# CH32F_V208G-R0.net
KiCad netlist of a schematic drawn in Altium Designer
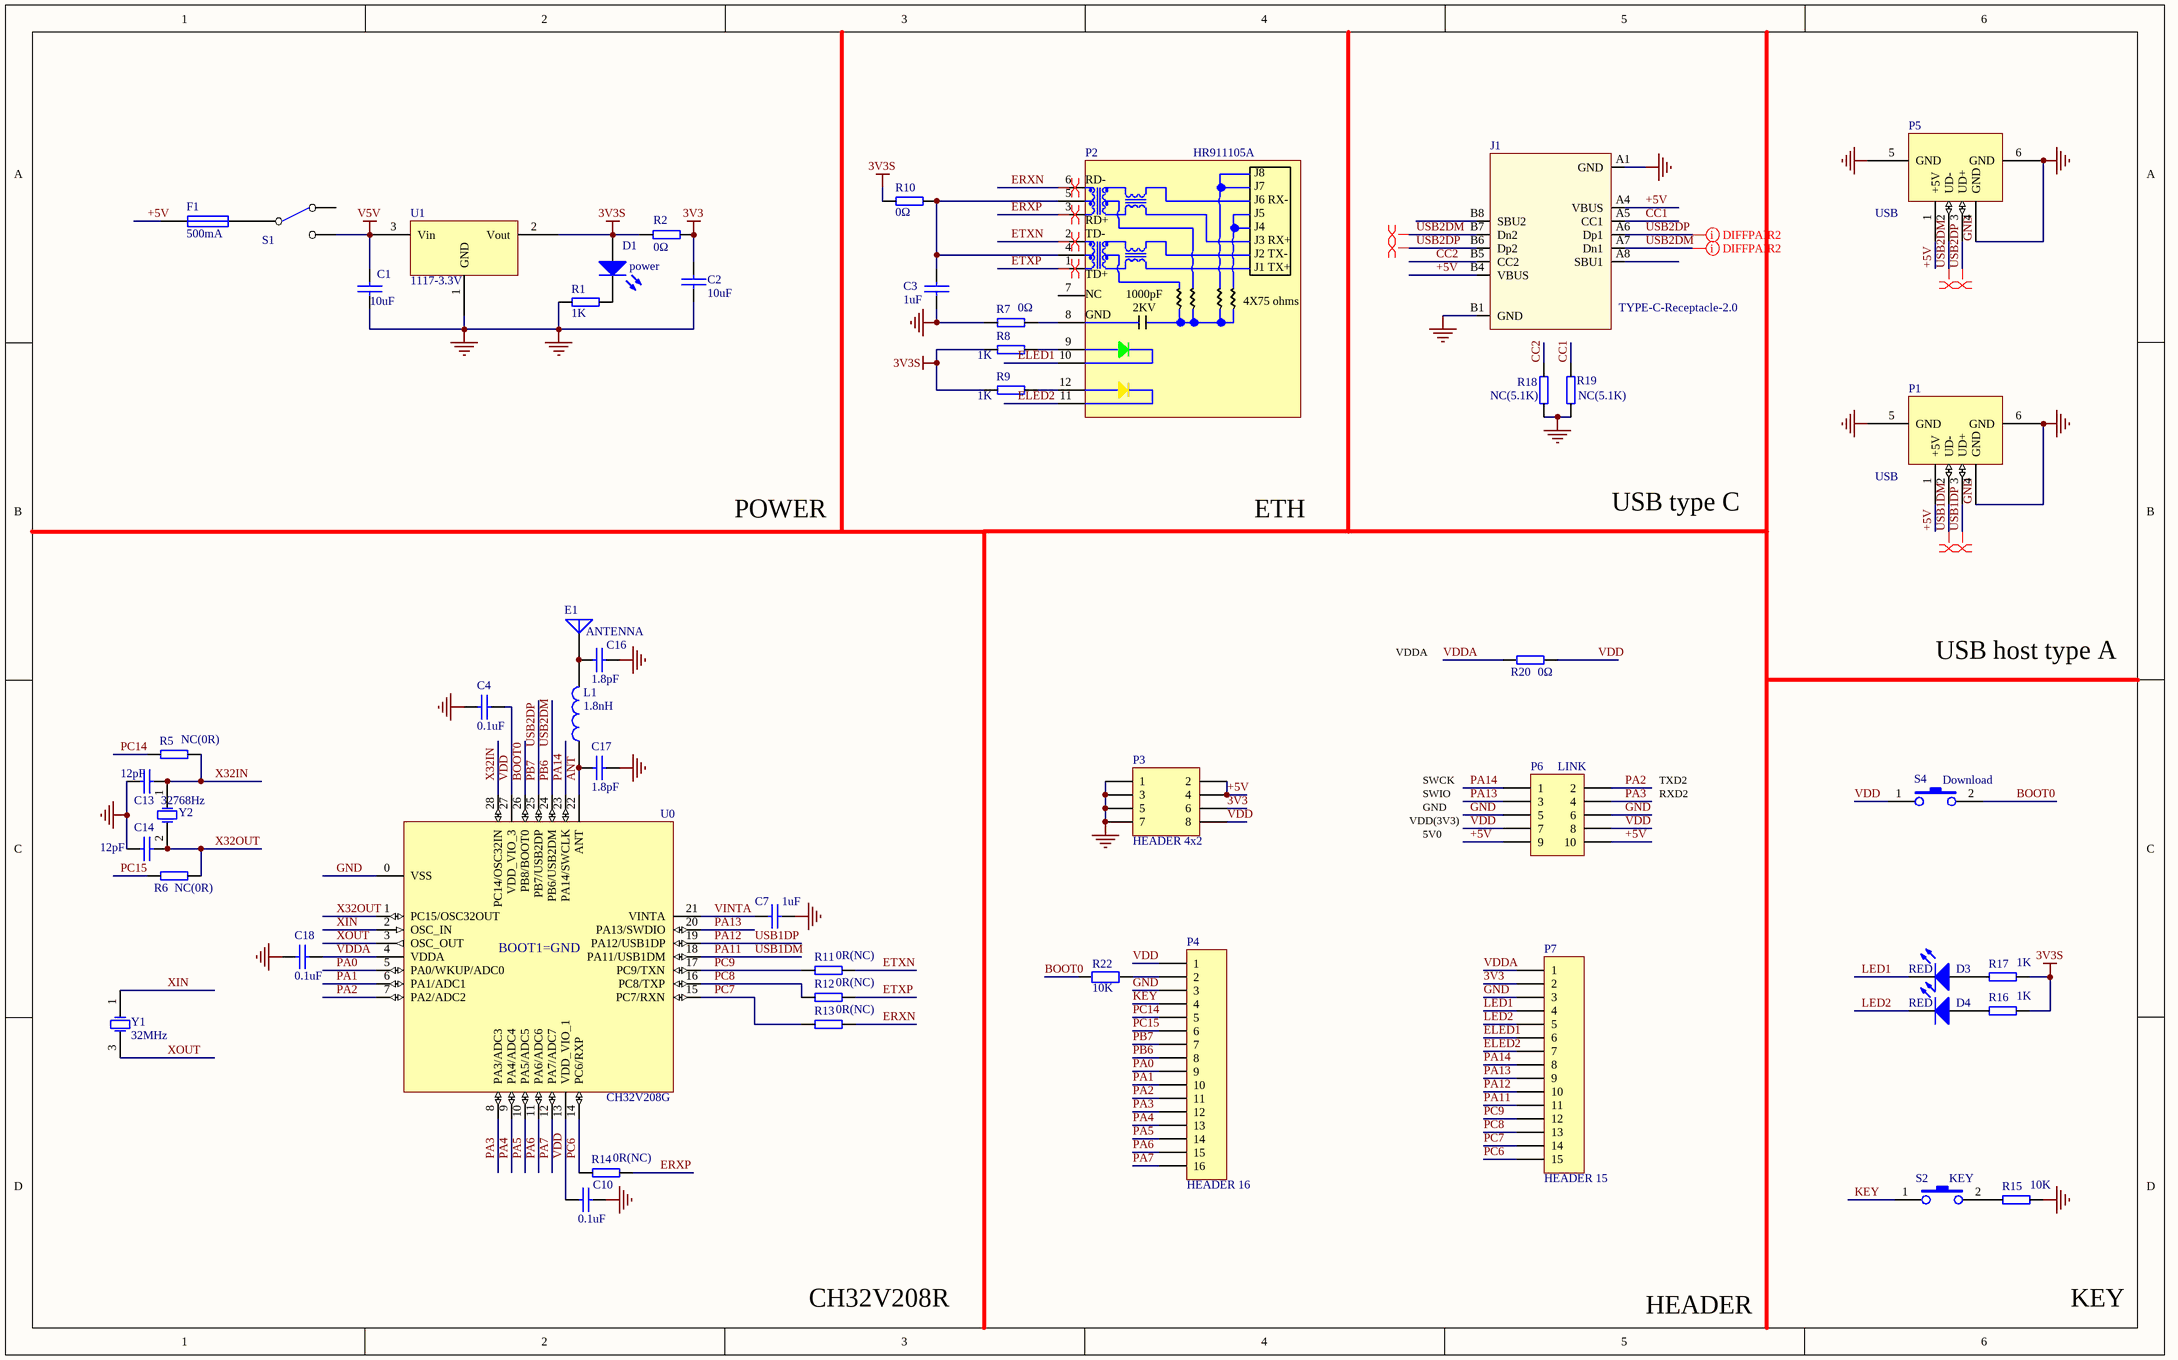
[diagram p0: CH32F&V208G-R0.SchDoc]

(export (version "E")
  (design (tool "Eeschema 10.0.6"))
  (components
    (comp (ref "C1")
      (value "10uF")
      (footprint "3216_C")
      (description "Capacitor")
      (libsource (lib "") (part "CAP_1"))
    )
    (comp (ref "C2")
      (value "10uF")
      (footprint "0603_C")
      (description "Capacitor")
      (libsource (lib "") (part "CAP_1"))
    )
    (comp (ref "C3")
      (value "1uF")
      (footprint "0603_C")
      (description "Capacitor")
      (libsource (lib "") (part "CAP_1"))
    )
    (comp (ref "C4")
      (value "0.1uF")
      (footprint "0603_C")
      (description "Capacitor")
      (libsource (lib "*") (part "CAP"))
    )
    (comp (ref "C7")
      (value "1uF")
      (footprint "0603_C")
      (description "Capacitor")
      (libsource (lib "*") (part "CAP"))
    )
    (comp (ref "C10")
      (value "0.1uF")
      (footprint "0603_C")
      (description "Capacitor")
      (libsource (lib "*") (part "CAP"))
    )
    (comp (ref "C13")
      (value "12pF")
      (footprint "0603_C")
      (description "Capacitor")
      (libsource (lib "") (part "CAP_1"))
    )
    (comp (ref "C14")
      (value "12pF")
      (footprint "0603_C")
      (description "Capacitor")
      (libsource (lib "") (part "CAP_1"))
    )
    (comp (ref "C16")
      (value "1.8pF")
      (footprint "0603_C")
      (description "Capacitor")
      (libsource (lib "*") (part "CAP"))
    )
    (comp (ref "C17")
      (value "1.8pF")
      (footprint "0603_C")
      (description "Capacitor")
      (libsource (lib "*") (part "CAP"))
    )
    (comp (ref "C18")
      (value "0.1uF")
      (footprint "0603_C")
      (description "Capacitor")
      (libsource (lib "*") (part "CAP"))
    )
    (comp (ref "D1")
      (value "power")
      (footprint "0603+")
      (description "Typical INFRARED GaAs LED")
      (fields (field (name "PUBLISHER") "Altium Limited"))
      (libsource (lib "*") (part "LED0"))
    )
    (comp (ref "D3")
      (value "RED")
      (footprint "0603+")
      (description "Typical INFRARED GaAs LED")
      (fields (field (name "PUBLISHER") "Altium Limited"))
      (libsource (lib "*") (part "LED0"))
    )
    (comp (ref "D4")
      (value "RED")
      (footprint "0603+")
      (description "Typical INFRARED GaAs LED")
      (fields (field (name "PUBLISHER") "Altium Limited"))
      (libsource (lib "*") (part "LED0"))
    )
    (comp (ref "E1")
      (value "ANTENNA")
      (footprint "ANT-F-1-2.4G-1.6mmFR4")
      (description "Generic Antenna")
      (libsource (lib "*") (part "ANTENNA"))
    )
    (comp (ref "F1")
      (value "500mA")
      (footprint "0603")
      (description "Fuse")
      (libsource (lib "wch_sch_others") (part "FUSE1"))
    )
    (comp (ref "J1")
      (value "TYPE-C-Receptacle-2.0")
      (footprint "TYPE-C-Receptacle-2.0")
      (description "Type-C USB2.0 母座")
      (libsource (lib "Miscellaneous SCH Lib") (part "TYPE-C-Receptacle-2.0"))
    )
    (comp (ref "L1") (value "1.8nH") (footprint "0603") (libsource (lib "*") (part "INDUCTOR")))
    (comp (ref "P1")
      (value "USB")
      (footprint "USBAF")
      (description "USB Port")
      (libsource (lib "*") (part "USB"))
    )
    (comp (ref "P2") (value "HR911105A") (footprint "HR911105A") (libsource (lib "*") (part "HR911105A")))
    (comp (ref "P3")
      (value "HEADER 4x2")
      (footprint "MYPCB:IDC8-2.54mm")
      (description "Header, 4-Pin, Dual row")
      (libsource (lib "wch_sch_others") (part "HEADER 4x2"))
    )
    (comp (ref "P4")
      (value "HEADER 16")
      (footprint "SIP16-2.54mm")
      (description "Header, 16-Pin")
      (libsource (lib "wch_sch_others") (part "HEADER 16"))
    )
    (comp (ref "P5")
      (value "USB")
      (footprint "USBAF")
      (description "USB Port")
      (libsource (lib "*") (part "USB"))
    )
    (comp (ref "P6")
      (value "LINK")
      (footprint "IDC10-2.54mm")
      (description "Header, 5-Pin, Dual row, Right Angle")
      (fields (field (name "PUBLISHER") "Altium Limited"))
      (libsource (lib "Miscellaneous Connectors") (part "Header 5X2H"))
    )
    (comp (ref "P7")
      (value "HEADER 15")
      (footprint "SIP15-2.54mm")
      (description "Header, 15-Pin")
      (libsource (lib "wch_sch_others") (part "HEADER 15"))
    )
    (comp (ref "R1") (value "1K") (footprint "0603") (libsource (lib "wch_sch_others") (part "RES")))
    (comp (ref "R2") (value "0Ω") (footprint "0603") (libsource (lib "wch_sch_others") (part "RES")))
    (comp (ref "R5") (value "NC(0R)") (footprint "0603") (libsource (lib "wch_sch_others") (part "RES")))
    (comp (ref "R6") (value "NC(0R)") (footprint "0603") (libsource (lib "wch_sch_others") (part "RES")))
    (comp (ref "R7") (value "0Ω") (footprint "0603") (libsource (lib "wch_sch_others") (part "RES")))
    (comp (ref "R8") (value "1K") (footprint "0603") (libsource (lib "wch_sch_others") (part "RES")))
    (comp (ref "R9") (value "1K") (footprint "0603") (libsource (lib "wch_sch_others") (part "RES")))
    (comp (ref "R10") (value "0Ω") (footprint "0603") (libsource (lib "wch_sch_others") (part "RES")))
    (comp (ref "R11") (value "0R(NC)") (footprint "0603") (libsource (lib "wch_sch_others") (part "RES")))
    (comp (ref "R12") (value "0R(NC)") (footprint "0603") (libsource (lib "wch_sch_others") (part "RES")))
    (comp (ref "R13") (value "0R(NC)") (footprint "0603") (libsource (lib "wch_sch_others") (part "RES")))
    (comp (ref "R14") (value "0R(NC)") (footprint "0603") (libsource (lib "wch_sch_others") (part "RES")))
    (comp (ref "R15") (value "10K") (footprint "0603") (libsource (lib "wch_sch_others") (part "RES")))
    (comp (ref "R16") (value "1K") (footprint "0603") (libsource (lib "wch_sch_others") (part "RES")))
    (comp (ref "R17") (value "1K") (footprint "0603") (libsource (lib "wch_sch_others") (part "RES")))
    (comp (ref "R18") (value "NC(5.1K)") (footprint "0603") (libsource (lib "wch_sch_others") (part "RES")))
    (comp (ref "R19") (value "NC(5.1K)") (footprint "0603") (libsource (lib "wch_sch_others") (part "RES")))
    (comp (ref "R20") (value "0Ω") (footprint "0603") (libsource (lib "*") (part "R")))
    (comp (ref "R22")
      (value "10K")
      (footprint "0603")
      (description "Resistor")
      (libsource (lib "Miscellaneous Devices") (part "Res2"))
    )
    (comp (ref "S1") (value "SW SPDT") (footprint "SW1") (libsource (lib "*") (part "SW SPDT")))
    (comp (ref "S2")
      (value "KEY")
      (footprint "SMD_6.1x3.65x2.5mm-KEY")
      (libsource (lib "wch_sch_others") (part "KEY1"))
    )
    (comp (ref "S4")
      (value "Download")
      (footprint "SMD_6.1x3.65x2.5mm-KEY")
      (libsource (lib "wch_sch_others") (part "KEY1"))
    )
    (comp (ref "U0")
      (value "CH32V208G")
      (footprint "QFN28_4x4")
      (description "RISC-V BLE5.3 MCU, 10M Ethernet, 2*USB, CAN")
      (libsource (lib "CHXXX") (part "CH32V208G"))
    )
    (comp (ref "U1")
      (value "1117-3.3V")
      (footprint "SOT-223")
      (libsource (lib "wch_sch_others") (part "1117-3.3V"))
    )
    (comp (ref "Y1")
      (value "32MHz")
      (footprint "XT3225")
      (description "Crystal Oscillator")
      (fields (field (name "PUBLISHER") "Altium Limited"))
      (libsource (lib "") (part "XTAL_1"))
    )
    (comp (ref "Y2")
      (value "32768Hz")
      (footprint "FC-135")
      (description "Crystal Oscillator")
      (fields (field (name "PUBLISHER") "Altium Limited"))
      (libsource (lib "*") (part "XTAL"))
    )
  )
  (nets
    (net (code "1") (name "/+5V") (class "Default")
      (node (ref "F1") (pin "1") (pinfunction "1_1") (pintype "passive"))
      (node (ref "J1") (pin "A4") (pinfunction "VBUS_A4") (pintype "passive"))
      (node (ref "J1") (pin "B4") (pinfunction "VBUS_B4") (pintype "passive"))
      (node (ref "P1") (pin "1") (pinfunction "+5V_1") (pintype "power_in"))
      (node (ref "P3") (pin "2") (pinfunction "2_2") (pintype "passive"))
      (node (ref "P3") (pin "4") (pinfunction "4_4") (pintype "passive"))
      (node (ref "P5") (pin "1") (pinfunction "+5V_1") (pintype "power_in"))
      (node (ref "P6") (pin "10") (pinfunction "10_10") (pintype "passive"))
      (node (ref "P6") (pin "9") (pinfunction "9_9") (pintype "passive"))
    )
    (net (code "2") (name "/ANT") (class "Default")
      (node (ref "C17") (pin "2") (pinfunction "2_2") (pintype "passive"))
      (node (ref "L1") (pin "1") (pinfunction "1_1") (pintype "passive"))
      (node (ref "U0") (pin "22") (pinfunction "ANT_22") (pintype "power_in"))
    )
    (net (code "3") (name "/BOOT0") (class "Default")
      (node (ref "R22") (pin "1") (pinfunction "1_1") (pintype "passive"))
      (node (ref "S4") (pin "2") (pinfunction "2_2") (pintype "passive"))
      (node (ref "U0") (pin "26") (pinfunction "PB8/BOOT0_26") (pintype "bidirectional"))
    )
    (net (code "4") (name "/CC1") (class "Default")
      (node (ref "J1") (pin "A5") (pinfunction "CC1_A5") (pintype "passive"))
      (node (ref "R19") (pin "1") (pintype "passive"))
    )
    (net (code "5") (name "/CC2") (class "Default")
      (node (ref "J1") (pin "B5") (pinfunction "CC2_B5") (pintype "passive"))
      (node (ref "R18") (pin "1") (pintype "passive"))
    )
    (net (code "6") (name "/ELED1") (class "Default")
      (node (ref "P2") (pin "10") (pintype "passive"))
      (node (ref "P7") (pin "6") (pinfunction "6_6") (pintype "passive"))
    )
    (net (code "7") (name "/ELED2") (class "Default")
      (node (ref "P2") (pin "11") (pintype "passive"))
      (node (ref "P7") (pin "7") (pinfunction "7_7") (pintype "passive"))
    )
    (net (code "8") (name "/ERXN") (class "Default")
      (node (ref "P2") (pin "6") (pintype "passive"))
      (node (ref "R13") (pin "2") (pintype "passive"))
    )
    (net (code "9") (name "/ERXP") (class "Default")
      (node (ref "P2") (pin "3") (pintype "passive"))
      (node (ref "R14") (pin "2") (pintype "passive"))
    )
    (net (code "10") (name "/ETXN") (class "Default")
      (node (ref "P2") (pin "2") (pintype "passive"))
      (node (ref "R11") (pin "2") (pintype "passive"))
    )
    (net (code "11") (name "/ETXP") (class "Default")
      (node (ref "P2") (pin "1") (pintype "passive"))
      (node (ref "R12") (pin "2") (pintype "passive"))
    )
    (net (code "12") (name "/KEY") (class "Default")
      (node (ref "P4") (pin "4") (pinfunction "4_4") (pintype "passive"))
      (node (ref "S2") (pin "1") (pinfunction "1_1") (pintype "passive"))
    )
    (net (code "13") (name "/LED1") (class "Default")
      (node (ref "D3") (pin "2") (pinfunction "K_2") (pintype "passive"))
      (node (ref "P7") (pin "4") (pinfunction "4_4") (pintype "passive"))
    )
    (net (code "14") (name "/LED2") (class "Default")
      (node (ref "D4") (pin "2") (pinfunction "K_2") (pintype "passive"))
      (node (ref "P7") (pin "5") (pinfunction "5_5") (pintype "passive"))
    )
    (net (code "15") (name "/PA0") (class "Default")
      (node (ref "P4") (pin "9") (pinfunction "9_9") (pintype "passive"))
      (node (ref "U0") (pin "5") (pinfunction "PA0/WKUP/ADC0_5") (pintype "bidirectional"))
    )
    (net (code "16") (name "/PA1") (class "Default")
      (node (ref "P4") (pin "10") (pinfunction "10_10") (pintype "passive"))
      (node (ref "U0") (pin "6") (pinfunction "PA1/ADC1_6") (pintype "bidirectional"))
    )
    (net (code "17") (name "/PA2") (class "Default")
      (node (ref "P4") (pin "11") (pinfunction "11_11") (pintype "passive"))
      (node (ref "P6") (pin "2") (pinfunction "2_2") (pintype "passive"))
      (node (ref "U0") (pin "7") (pinfunction "PA2/ADC2_7") (pintype "bidirectional"))
    )
    (net (code "18") (name "/PA3") (class "Default")
      (node (ref "P4") (pin "12") (pinfunction "12_12") (pintype "passive"))
      (node (ref "P6") (pin "4") (pinfunction "4_4") (pintype "passive"))
      (node (ref "U0") (pin "8") (pinfunction "PA3/ADC3_8") (pintype "bidirectional"))
    )
    (net (code "19") (name "/PA4") (class "Default")
      (node (ref "P4") (pin "13") (pinfunction "13_13") (pintype "passive"))
      (node (ref "U0") (pin "9") (pinfunction "PA4/ADC4_9") (pintype "bidirectional"))
    )
    (net (code "20") (name "/PA5") (class "Default")
      (node (ref "P4") (pin "14") (pinfunction "14_14") (pintype "passive"))
      (node (ref "U0") (pin "10") (pinfunction "PA5/ADC5_10") (pintype "bidirectional"))
    )
    (net (code "21") (name "/PA6") (class "Default")
      (node (ref "P4") (pin "15") (pinfunction "15_15") (pintype "passive"))
      (node (ref "U0") (pin "11") (pinfunction "PA6/ADC6_11") (pintype "bidirectional"))
    )
    (net (code "22") (name "/PA7") (class "Default")
      (node (ref "P4") (pin "16") (pinfunction "16_16") (pintype "passive"))
      (node (ref "U0") (pin "12") (pinfunction "PA7/ADC7_12") (pintype "bidirectional"))
    )
    (net (code "23") (name "/PA11") (class "Default")
      (node (ref "P1") (pin "2") (pinfunction "UD-_2") (pintype "bidirectional"))
      (node (ref "P7") (pin "11") (pinfunction "11_11") (pintype "passive"))
      (node (ref "U0") (pin "18") (pinfunction "PA11/USB1DM_18") (pintype "bidirectional"))
    )
    (net (code "24") (name "/PA12") (class "Default")
      (node (ref "P1") (pin "3") (pinfunction "UD+_3") (pintype "bidirectional"))
      (node (ref "P7") (pin "10") (pinfunction "10_10") (pintype "passive"))
      (node (ref "U0") (pin "19") (pinfunction "PA12/USB1DP_19") (pintype "bidirectional"))
    )
    (net (code "25") (name "/PA13") (class "Default")
      (node (ref "P6") (pin "3") (pinfunction "3_3") (pintype "passive"))
      (node (ref "P7") (pin "9") (pinfunction "9_9") (pintype "passive"))
      (node (ref "U0") (pin "20") (pinfunction "PA13/SWDIO_20") (pintype "bidirectional"))
    )
    (net (code "26") (name "/PA14") (class "Default")
      (node (ref "P6") (pin "1") (pinfunction "1_1") (pintype "passive"))
      (node (ref "P7") (pin "8") (pinfunction "8_8") (pintype "passive"))
      (node (ref "U0") (pin "23") (pinfunction "PA14/SWCLK_23") (pintype "bidirectional"))
    )
    (net (code "27") (name "/PB6") (class "Default")
      (node (ref "J1") (pin "A7") (pinfunction "Dn1_A7") (pintype "passive"))
      (node (ref "J1") (pin "B7") (pinfunction "Dn2_B7") (pintype "passive"))
      (node (ref "P4") (pin "8") (pinfunction "8_8") (pintype "passive"))
      (node (ref "P5") (pin "2") (pinfunction "UD-_2") (pintype "bidirectional"))
      (node (ref "U0") (pin "24") (pinfunction "PB6/USB2DM_24") (pintype "bidirectional"))
    )
    (net (code "28") (name "/PB7") (class "Default")
      (node (ref "J1") (pin "A6") (pinfunction "Dp1_A6") (pintype "passive"))
      (node (ref "J1") (pin "B6") (pinfunction "Dp2_B6") (pintype "passive"))
      (node (ref "P4") (pin "7") (pinfunction "7_7") (pintype "passive"))
      (node (ref "P5") (pin "3") (pinfunction "UD+_3") (pintype "bidirectional"))
      (node (ref "U0") (pin "25") (pinfunction "PB7/USB2DP_25") (pintype "bidirectional"))
    )
    (net (code "29") (name "/PC6") (class "Default")
      (node (ref "P7") (pin "15") (pinfunction "15_15") (pintype "passive"))
      (node (ref "R14") (pin "1") (pintype "passive"))
      (node (ref "U0") (pin "14") (pinfunction "PC6/RXP_14") (pintype "bidirectional"))
    )
    (net (code "30") (name "/PC7") (class "Default")
      (node (ref "P7") (pin "14") (pinfunction "14_14") (pintype "passive"))
      (node (ref "R13") (pin "1") (pintype "passive"))
      (node (ref "U0") (pin "15") (pinfunction "PC7/RXN_15") (pintype "bidirectional"))
    )
    (net (code "31") (name "/PC8") (class "Default")
      (node (ref "P7") (pin "13") (pinfunction "13_13") (pintype "passive"))
      (node (ref "R12") (pin "1") (pintype "passive"))
      (node (ref "U0") (pin "16") (pinfunction "PC8/TXP_16") (pintype "bidirectional"))
    )
    (net (code "32") (name "/PC9") (class "Default")
      (node (ref "P7") (pin "12") (pinfunction "12_12") (pintype "passive"))
      (node (ref "R11") (pin "1") (pintype "passive"))
      (node (ref "U0") (pin "17") (pinfunction "PC9/TXN_17") (pintype "bidirectional"))
    )
    (net (code "33") (name "/PC14") (class "Default")
      (node (ref "P4") (pin "5") (pinfunction "5_5") (pintype "passive"))
      (node (ref "R5") (pin "1") (pintype "passive"))
    )
    (net (code "34") (name "/PC15") (class "Default")
      (node (ref "P4") (pin "6") (pinfunction "6_6") (pintype "passive"))
      (node (ref "R6") (pin "1") (pintype "passive"))
    )
    (net (code "35") (name "/VDD") (class "Default")
      (node (ref "C10") (pin "2") (pinfunction "2_2") (pintype "passive"))
      (node (ref "C4") (pin "1") (pinfunction "1_1") (pintype "passive"))
      (node (ref "P3") (pin "8") (pinfunction "8_8") (pintype "passive"))
      (node (ref "P4") (pin "1") (pinfunction "1_1") (pintype "passive"))
      (node (ref "P6") (pin "7") (pinfunction "7_7") (pintype "passive"))
      (node (ref "P6") (pin "8") (pinfunction "8_8") (pintype "passive"))
      (node (ref "R20") (pin "1") (pinfunction "1_1") (pintype "passive"))
      (node (ref "S4") (pin "1") (pinfunction "1_1") (pintype "passive"))
      (node (ref "U0") (pin "13") (pinfunction "VDD_VIO_1_13") (pintype "power_in"))
      (node (ref "U0") (pin "27") (pinfunction "VDD_VIO_3_27") (pintype "power_in"))
    )
    (net (code "36") (name "/VDDA") (class "Default")
      (node (ref "C18") (pin "1") (pinfunction "1_1") (pintype "passive"))
      (node (ref "P7") (pin "1") (pinfunction "1_1") (pintype "passive"))
      (node (ref "R20") (pin "2") (pinfunction "2_2") (pintype "passive"))
      (node (ref "U0") (pin "4") (pinfunction "VDDA_4") (pintype "power_in"))
    )
    (net (code "37") (name "/VINTA") (class "Default")
      (node (ref "C7") (pin "1") (pinfunction "1_1") (pintype "passive"))
      (node (ref "U0") (pin "21") (pinfunction "VINTA_21") (pintype "power_in"))
    )
    (net (code "38") (name "/X32IN") (class "Default")
      (node (ref "C13") (pin "2") (pinfunction "2_2") (pintype "passive"))
      (node (ref "R5") (pin "2") (pintype "passive"))
      (node (ref "U0") (pin "28") (pinfunction "PC14/OSC32IN_28") (pintype "bidirectional"))
      (node (ref "Y2") (pin "1") (pinfunction "OSC1_1") (pintype "passive"))
    )
    (net (code "39") (name "/X32OUT") (class "Default")
      (node (ref "C14") (pin "2") (pinfunction "2_2") (pintype "passive"))
      (node (ref "R6") (pin "2") (pintype "passive"))
      (node (ref "U0") (pin "1") (pinfunction "PC15/OSC32OUT_1") (pintype "bidirectional"))
      (node (ref "Y2") (pin "2") (pinfunction "OSC2_2") (pintype "passive"))
    )
    (net (code "40") (name "/XIN") (class "Default")
      (node (ref "U0") (pin "2") (pinfunction "OSC_IN_2") (pintype "input"))
      (node (ref "Y1") (pin "1") (pinfunction "OSC1_1") (pintype "passive"))
    )
    (net (code "41") (name "/XOUT") (class "Default")
      (node (ref "U0") (pin "3") (pinfunction "OSC_OUT_3") (pintype "output"))
      (node (ref "Y1") (pin "3") (pinfunction "OSC2_3") (pintype "passive"))
    )
    (net (code "42") (name "3V3") (class "Default")
      (node (ref "C2") (pin "1") (pinfunction "1_1") (pintype "passive"))
      (node (ref "P3") (pin "6") (pinfunction "6_6") (pintype "passive"))
      (node (ref "P7") (pin "2") (pinfunction "2_2") (pintype "passive"))
      (node (ref "R2") (pin "1") (pintype "passive"))
    )
    (net (code "43") (name "3V3S") (class "Default")
      (node (ref "D1") (pin "1") (pinfunction "A_1") (pintype "passive"))
      (node (ref "R10") (pin "2") (pintype "passive"))
      (node (ref "R16") (pin "1") (pintype "passive"))
      (node (ref "R17") (pin "1") (pintype "passive"))
      (node (ref "R2") (pin "2") (pintype "passive"))
      (node (ref "R8") (pin "1") (pintype "passive"))
      (node (ref "R9") (pin "1") (pintype "passive"))
      (node (ref "U1") (pin "2") (pinfunction "Vout_2") (pintype "passive"))
    )
    (net (code "44") (name "GND") (class "Default")
      (node (ref "C1") (pin "2") (pinfunction "2_2") (pintype "passive"))
      (node (ref "C10") (pin "1") (pinfunction "1_1") (pintype "passive"))
      (node (ref "C13") (pin "1") (pinfunction "1_1") (pintype "passive"))
      (node (ref "C14") (pin "1") (pinfunction "1_1") (pintype "passive"))
      (node (ref "C16") (pin "1") (pinfunction "1_1") (pintype "passive"))
      (node (ref "C17") (pin "1") (pinfunction "1_1") (pintype "passive"))
      (node (ref "C18") (pin "2") (pinfunction "2_2") (pintype "passive"))
      (node (ref "C2") (pin "2") (pinfunction "2_2") (pintype "passive"))
      (node (ref "C3") (pin "1") (pinfunction "1_1") (pintype "passive"))
      (node (ref "C4") (pin "2") (pinfunction "2_2") (pintype "passive"))
      (node (ref "C7") (pin "2") (pinfunction "2_2") (pintype "passive"))
      (node (ref "J1") (pin "A1") (pinfunction "GND_A1") (pintype "passive"))
      (node (ref "J1") (pin "B1") (pinfunction "GND_B1") (pintype "passive"))
      (node (ref "P1") (pin "4") (pinfunction "GND_4") (pintype "power_in"))
      (node (ref "P1") (pin "5") (pinfunction "GND_5") (pintype "power_in"))
      (node (ref "P1") (pin "6") (pinfunction "GND_6") (pintype "power_in"))
      (node (ref "P3") (pin "1") (pinfunction "1_1") (pintype "passive"))
      (node (ref "P3") (pin "3") (pinfunction "3_3") (pintype "passive"))
      (node (ref "P3") (pin "5") (pinfunction "5_5") (pintype "passive"))
      (node (ref "P3") (pin "7") (pinfunction "7_7") (pintype "passive"))
      (node (ref "P4") (pin "3") (pinfunction "3_3") (pintype "passive"))
      (node (ref "P5") (pin "4") (pinfunction "GND_4") (pintype "power_in"))
      (node (ref "P5") (pin "5") (pinfunction "GND_5") (pintype "power_in"))
      (node (ref "P5") (pin "6") (pinfunction "GND_6") (pintype "power_in"))
      (node (ref "P6") (pin "5") (pinfunction "5_5") (pintype "passive"))
      (node (ref "P6") (pin "6") (pinfunction "6_6") (pintype "passive"))
      (node (ref "P7") (pin "3") (pinfunction "3_3") (pintype "passive"))
      (node (ref "R1") (pin "1") (pintype "passive"))
      (node (ref "R15") (pin "1") (pintype "passive"))
      (node (ref "R18") (pin "2") (pintype "passive"))
      (node (ref "R19") (pin "2") (pintype "passive"))
      (node (ref "R7") (pin "1") (pintype "passive"))
      (node (ref "U0") (pin "0") (pinfunction "VSS_0") (pintype "power_in"))
      (node (ref "U1") (pin "1") (pinfunction "GND_1") (pintype "passive"))
    )
    (net (code "45") (name "Net-(C3-Pad2)") (class "Default")
      (node (ref "C3") (pin "2") (pinfunction "2_2") (pintype "passive"))
      (node (ref "P2") (pin "4") (pintype "passive"))
      (node (ref "P2") (pin "5") (pintype "passive"))
      (node (ref "R10") (pin "1") (pintype "passive"))
    )
    (net (code "46") (name "Net-(D1-K)") (class "Default")
      (node (ref "D1") (pin "2") (pinfunction "K_2") (pintype "passive"))
      (node (ref "R1") (pin "2") (pintype "passive"))
    )
    (net (code "47") (name "Net-(D3-A)") (class "Default")
      (node (ref "D3") (pin "1") (pinfunction "A_1") (pintype "passive"))
      (node (ref "R17") (pin "2") (pintype "passive"))
    )
    (net (code "48") (name "Net-(D4-A)") (class "Default")
      (node (ref "D4") (pin "1") (pinfunction "A_1") (pintype "passive"))
      (node (ref "R16") (pin "2") (pintype "passive"))
    )
    (net (code "49") (name "Net-(E1-A)") (class "Default")
      (node (ref "C16") (pin "2") (pinfunction "2_2") (pintype "passive"))
      (node (ref "E1") (pin "1") (pinfunction "A_1") (pintype "passive"))
      (node (ref "L1") (pin "2") (pinfunction "2_2") (pintype "passive"))
    )
    (net (code "50") (name "Net-(P2-Pad8)") (class "Default")
      (node (ref "P2") (pin "8") (pintype "passive"))
      (node (ref "R7") (pin "2") (pintype "passive"))
    )
    (net (code "51") (name "Net-(P2-Pad9)") (class "Default")
      (node (ref "P2") (pin "9") (pintype "passive"))
      (node (ref "R8") (pin "2") (pintype "passive"))
    )
    (net (code "52") (name "Net-(P2-Pad12)") (class "Default")
      (node (ref "P2") (pin "12") (pintype "passive"))
      (node (ref "R9") (pin "2") (pintype "passive"))
    )
    (net (code "53") (name "Net-(P4-Pad2)") (class "Default")
      (node (ref "P4") (pin "2") (pinfunction "2_2") (pintype "passive"))
      (node (ref "R22") (pin "2") (pinfunction "2_2") (pintype "passive"))
    )
    (net (code "54") (name "Net-(R15-Pad2)") (class "Default")
      (node (ref "R15") (pin "2") (pintype "passive"))
      (node (ref "S2") (pin "2") (pinfunction "2_2") (pintype "passive"))
    )
    (net (code "55") (name "Net-(S1-COMMON)") (class "Default")
      (node (ref "F1") (pin "2") (pinfunction "2_2") (pintype "passive"))
      (node (ref "S1") (pin "1") (pinfunction "COMMON_1") (pintype "passive"))
    )
    (net (code "56") (name "V5V") (class "Default")
      (node (ref "C1") (pin "1") (pinfunction "1_1") (pintype "passive"))
      (node (ref "S1") (pin "2") (pinfunction "NC_2") (pintype "passive"))
      (node (ref "U1") (pin "3") (pinfunction "Vin_3") (pintype "passive"))
    )
    (net (code "57") (name "unconnected-(J1-SBU1-PadA8)") (class "Default")
      (node (ref "J1") (pin "A8") (pinfunction "SBU1_A8") (pintype "passive"))
    )
    (net (code "58") (name "unconnected-(J1-SBU2-PadB8)") (class "Default")
      (node (ref "J1") (pin "B8") (pinfunction "SBU2_B8") (pintype "passive"))
    )
    (net (code "59") (name "unconnected-(P2-Pad7)") (class "Default")
      (node (ref "P2") (pin "7") (pintype "passive"))
    )
    (net (code "60") (name "unconnected-(S1-NO-Pad3)") (class "Default")
      (node (ref "S1") (pin "3") (pinfunction "NO_3") (pintype "passive"))
    )
  )
)
